# proto.net
KiCad netlist of a schematic drawn in EAGLE
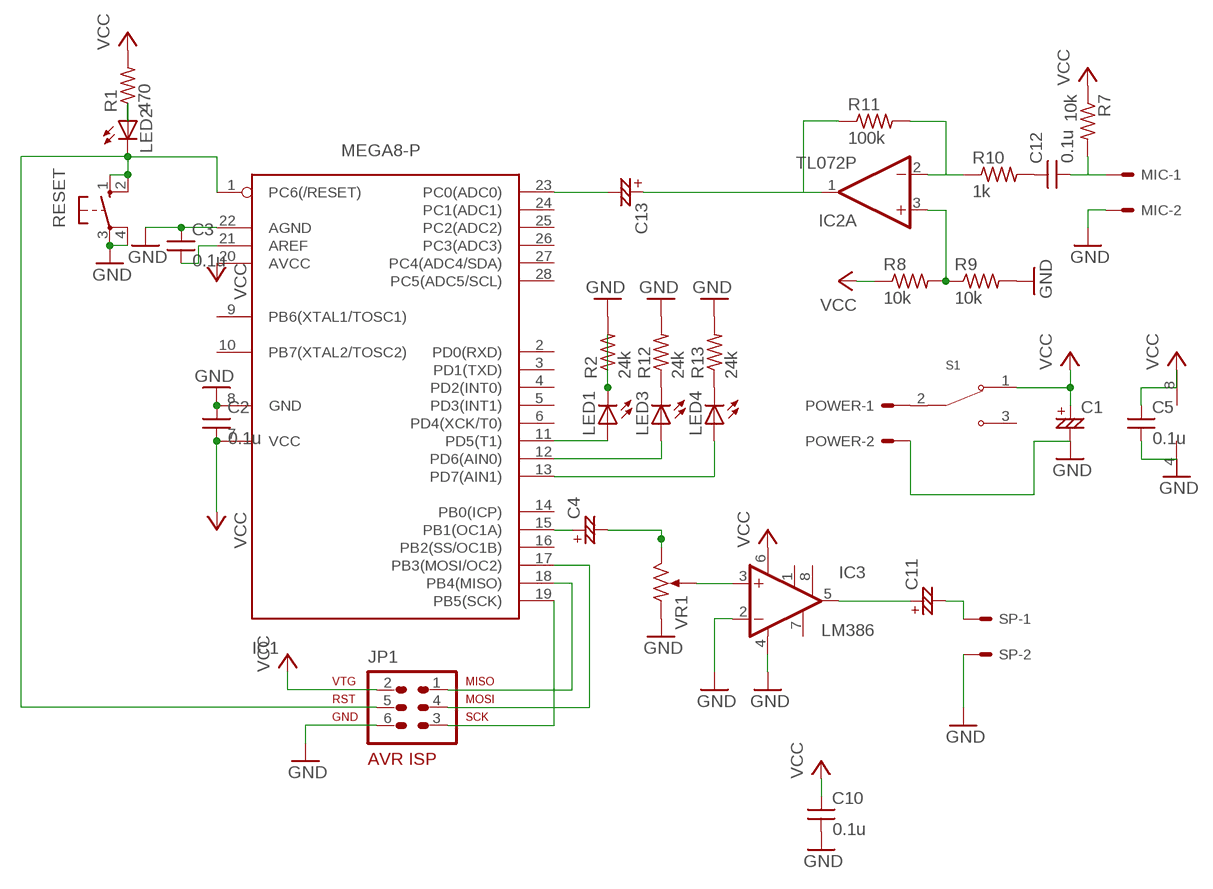
[diagram p0: schematic, sheet 1]

(export (version "E")
  (design (tool "Eeschema 10.0.6"))
  (components
    (comp (ref "C1")
      (value "E-CAPACITOR-2")
      (footprint "eagle-import:E3,5-8")
      (libsource (lib "eagle-import") (part "E-CAPACITOR-2"))
    )
    (comp (ref "C2")
      (value "0.1u")
      (footprint "eagle-import:C5B3")
      (libsource (lib "eagle-import") (part "C-CAPACITOR-2"))
    )
    (comp (ref "C3")
      (value "0.1u")
      (footprint "eagle-import:C5B3")
      (libsource (lib "eagle-import") (part "C-CAPACITOR-2"))
    )
    (comp (ref "C4")
      (value "E-CAPACITOR-2")
      (footprint "eagle-import:E3,5-8")
      (libsource (lib "eagle-import") (part "E-CAPACITOR-2"))
    )
    (comp (ref "C5")
      (value "0.1u")
      (footprint "eagle-import:C5B3")
      (libsource (lib "eagle-import") (part "C-CAPACITOR-2"))
    )
    (comp (ref "C10")
      (value "0.1u")
      (footprint "eagle-import:C5B3")
      (libsource (lib "eagle-import") (part "C-CAPACITOR-2"))
    )
    (comp (ref "C11")
      (value "E-CAPACITOR-2")
      (footprint "eagle-import:E3,5-8")
      (libsource (lib "eagle-import") (part "E-CAPACITOR-2"))
    )
    (comp (ref "C12")
      (value "0.1u")
      (footprint "eagle-import:C5B3")
      (libsource (lib "eagle-import") (part "C-CAPACITOR-2"))
    )
    (comp (ref "C13")
      (value "E-CAPACITOR-2")
      (footprint "eagle-import:E3,5-8")
      (libsource (lib "eagle-import") (part "E-CAPACITOR-2"))
    )
    (comp (ref "IC1")
      (value "MEGA8-P")
      (footprint "eagle-import:DIL28-3")
      (libsource (lib "eagle-import") (part "MEGA8-P"))
    )
    (comp (ref "IC2")
      (value "TL072P")
      (footprint "eagle-import:DIL08")
      (libsource (lib "eagle-import") (part "TL072P"))
    )
    (comp (ref "IC3")
      (value "LM386")
      (footprint "eagle-import:DIL08")
      (libsource (lib "eagle-import") (part "LM386"))
    )
    (comp (ref "JP1")
      (value "AVR-ISP-6")
      (footprint "eagle-import:AVR-ISP-6")
      (libsource (lib "eagle-import") (part "AVR-ISP-6"))
    )
    (comp (ref "LED1")
      (value "LED3MM")
      (footprint "eagle-import:LED3MM")
      (libsource (lib "eagle-import") (part "LED3MM"))
    )
    (comp (ref "LED2")
      (value "LED3MM")
      (footprint "eagle-import:LED3MM")
      (libsource (lib "eagle-import") (part "LED3MM"))
    )
    (comp (ref "LED3")
      (value "LED3MM")
      (footprint "eagle-import:LED3MM")
      (libsource (lib "eagle-import") (part "LED3MM"))
    )
    (comp (ref "LED4")
      (value "LED3MM")
      (footprint "eagle-import:LED3MM")
      (libsource (lib "eagle-import") (part "LED3MM"))
    )
    (comp (ref "MIC")
      (value "S2P-S")
      (footprint "eagle-import:2P-S")
      (libsource (lib "eagle-import") (part "S2P-S"))
    )
    (comp (ref "POWER")
      (value "S2P-S")
      (footprint "eagle-import:2P-S")
      (libsource (lib "eagle-import") (part "S2P-S"))
    )
    (comp (ref "R1")
      (value "470")
      (footprint "eagle-import:0207_3V")
      (libsource (lib "eagle-import") (part "RESISTOR-3V"))
    )
    (comp (ref "R2")
      (value "24k")
      (footprint "eagle-import:0207_3V")
      (libsource (lib "eagle-import") (part "RESISTOR-3V"))
    )
    (comp (ref "R7")
      (value "10k")
      (footprint "eagle-import:0207_3V")
      (libsource (lib "eagle-import") (part "RESISTOR-3V"))
    )
    (comp (ref "R8")
      (value "10k")
      (footprint "eagle-import:0207_3V")
      (libsource (lib "eagle-import") (part "RESISTOR-3V"))
    )
    (comp (ref "R9")
      (value "10k")
      (footprint "eagle-import:0207_3V")
      (libsource (lib "eagle-import") (part "RESISTOR-3V"))
    )
    (comp (ref "R10")
      (value "1k")
      (footprint "eagle-import:0207_3V")
      (libsource (lib "eagle-import") (part "RESISTOR-3V"))
    )
    (comp (ref "R11")
      (value "100k")
      (footprint "eagle-import:0207_3V")
      (libsource (lib "eagle-import") (part "RESISTOR-3V"))
    )
    (comp (ref "R12")
      (value "24k")
      (footprint "eagle-import:0207_3V")
      (libsource (lib "eagle-import") (part "RESISTOR-3V"))
    )
    (comp (ref "R13")
      (value "24k")
      (footprint "eagle-import:0207_3V")
      (libsource (lib "eagle-import") (part "RESISTOR-3V"))
    )
    (comp (ref "RESET")
      (value "10-XX")
      (footprint "eagle-import:B3F-10XX")
      (libsource (lib "eagle-import") (part "10-XX"))
    )
    (comp (ref "S1")
      (value "MS12ANW03")
      (footprint "eagle-import:SW_MS12ANW03")
      (fields (field (name "MF") "NKK Switches"))
      (libsource (lib "eagle-import") (part "MS12ANW03"))
    )
    (comp (ref "SP")
      (value "S2P-S")
      (footprint "eagle-import:2P-S")
      (libsource (lib "eagle-import") (part "S2P-S"))
    )
    (comp (ref "VR1")
      (value "V-RESISTOR")
      (footprint "eagle-import:B25X")
      (libsource (lib "eagle-import") (part "V-RESISTOR"))
    )
  )
  (nets
    (net (code "1") (name "/V-") (class "Default")
      (node (ref "IC2") (pin "4") (pinfunction "V-_4") (pintype "power_in"))
    )
    (net (code "2") (name "GND") (class "Default")
      (node (ref "C1") (pin "2") (pinfunction "2_2") (pintype "passive"))
      (node (ref "C10") (pin "2") (pinfunction "2_2") (pintype "passive"))
      (node (ref "C2") (pin "1") (pinfunction "1_1") (pintype "passive"))
      (node (ref "C3") (pin "1") (pinfunction "1_1") (pintype "passive"))
      (node (ref "C5") (pin "2") (pinfunction "2_2") (pintype "passive"))
      (node (ref "IC1") (pin "22") (pinfunction "AGND_22") (pintype "bidirectional"))
      (node (ref "IC1") (pin "8") (pinfunction "GND_8") (pintype "bidirectional"))
      (node (ref "IC3") (pin "2") (pinfunction "-IN_2") (pintype "input"))
      (node (ref "IC3") (pin "4") (pinfunction "V-_4") (pintype "power_in"))
      (node (ref "JP1") (pin "6") (pinfunction "6_6") (pintype "passive"))
      (node (ref "MIC") (pin "2") (pinfunction "S_2") (pintype "passive"))
      (node (ref "POWER") (pin "2") (pinfunction "S_2") (pintype "passive"))
      (node (ref "R12") (pin "2") (pinfunction "2_2") (pintype "passive"))
      (node (ref "R13") (pin "2") (pinfunction "2_2") (pintype "passive"))
      (node (ref "R2") (pin "2") (pinfunction "2_2") (pintype "passive"))
      (node (ref "R9") (pin "2") (pinfunction "2_2") (pintype "passive"))
      (node (ref "RESET") (pin "3") (pinfunction "P_3") (pintype "passive"))
      (node (ref "RESET") (pin "4") (pinfunction "P1_4") (pintype "passive"))
      (node (ref "SP") (pin "2") (pinfunction "S_2") (pintype "passive"))
      (node (ref "VR1") (pin "2") (pinfunction "2_2") (pintype "passive"))
    )
    (net (code "3") (name "Net-(C4-Pad2)") (class "Default")
      (node (ref "C4") (pin "2") (pinfunction "2_2") (pintype "passive"))
      (node (ref "VR1") (pin "1") (pinfunction "1_1") (pintype "passive"))
    )
    (net (code "4") (name "Net-(C12-Pad1)") (class "Default")
      (node (ref "C12") (pin "1") (pinfunction "1_1") (pintype "passive"))
      (node (ref "R10") (pin "2") (pinfunction "2_2") (pintype "passive"))
    )
    (net (code "5") (name "Net-(IC1-AREF)") (class "Default")
      (node (ref "C3") (pin "2") (pinfunction "2_2") (pintype "passive"))
      (node (ref "IC1") (pin "21") (pinfunction "AREF_21") (pintype "bidirectional"))
    )
    (net (code "6") (name "Net-(IC1-PB1(OC1A))") (class "Default")
      (node (ref "C4") (pin "1") (pinfunction "1_1") (pintype "passive"))
      (node (ref "IC1") (pin "15") (pinfunction "PB1(OC1A)_15") (pintype "bidirectional"))
    )
    (net (code "7") (name "Net-(IC1-PB3(MOSI{slash}OC2))") (class "Default")
      (node (ref "IC1") (pin "17") (pinfunction "PB3(MOSI/OC2)_17") (pintype "bidirectional"))
      (node (ref "JP1") (pin "4") (pinfunction "4_4") (pintype "passive"))
    )
    (net (code "8") (name "Net-(IC1-PB4(MISO))") (class "Default")
      (node (ref "IC1") (pin "18") (pinfunction "PB4(MISO)_18") (pintype "bidirectional"))
      (node (ref "JP1") (pin "1") (pinfunction "1_1") (pintype "passive"))
    )
    (net (code "9") (name "Net-(IC1-PB5(SCK))") (class "Default")
      (node (ref "IC1") (pin "19") (pinfunction "PB5(SCK)_19") (pintype "bidirectional"))
      (node (ref "JP1") (pin "3") (pinfunction "3_3") (pintype "passive"))
    )
    (net (code "10") (name "Net-(IC1-PC0(ADC0))") (class "Default")
      (node (ref "C13") (pin "2") (pinfunction "2_2") (pintype "passive"))
      (node (ref "IC1") (pin "23") (pinfunction "PC0(ADC0)_23") (pintype "bidirectional"))
    )
    (net (code "11") (name "Net-(IC1-PC6({slash}RESET))") (class "Default")
      (node (ref "IC1") (pin "1") (pinfunction "PC6(/RESET)_1") (pintype "bidirectional"))
      (node (ref "LED2") (pin "K") (pinfunction "C_K") (pintype "passive"))
      (node (ref "RESET") (pin "1") (pinfunction "S_1") (pintype "passive"))
      (node (ref "RESET") (pin "2") (pinfunction "S1_2") (pintype "passive"))
    )
    (net (code "12") (name "Net-(IC1-PD5(T1))") (class "Default")
      (node (ref "IC1") (pin "11") (pinfunction "PD5(T1)_11") (pintype "bidirectional"))
      (node (ref "LED1") (pin "A") (pinfunction "A_A") (pintype "passive"))
    )
    (net (code "13") (name "Net-(IC1-PD6(AIN0))") (class "Default")
      (node (ref "IC1") (pin "12") (pinfunction "PD6(AIN0)_12") (pintype "bidirectional"))
      (node (ref "LED3") (pin "A") (pinfunction "A_A") (pintype "passive"))
    )
    (net (code "14") (name "Net-(IC1-PD7(AIN1))") (class "Default")
      (node (ref "IC1") (pin "13") (pinfunction "PD7(AIN1)_13") (pintype "bidirectional"))
      (node (ref "LED4") (pin "A") (pinfunction "A_A") (pintype "passive"))
    )
    (net (code "15") (name "Net-(IC2A-+IN)") (class "Default")
      (node (ref "IC2") (pin "3") (pinfunction "+IN_3") (pintype "input"))
      (node (ref "R8") (pin "2") (pinfunction "2_2") (pintype "passive"))
      (node (ref "R9") (pin "1") (pinfunction "1_1") (pintype "passive"))
    )
    (net (code "16") (name "Net-(IC2A--IN)") (class "Default")
      (node (ref "IC2") (pin "2") (pinfunction "-IN_2") (pintype "input"))
      (node (ref "R10") (pin "1") (pinfunction "1_1") (pintype "passive"))
      (node (ref "R11") (pin "2") (pinfunction "2_2") (pintype "passive"))
    )
    (net (code "17") (name "Net-(IC2A-OUT)") (class "Default")
      (node (ref "C13") (pin "1") (pinfunction "1_1") (pintype "passive"))
      (node (ref "IC2") (pin "1") (pinfunction "OUT_1") (pintype "output"))
      (node (ref "R11") (pin "1") (pinfunction "1_1") (pintype "passive"))
    )
    (net (code "18") (name "Net-(IC3-+IN)") (class "Default")
      (node (ref "IC3") (pin "3") (pinfunction "+IN_3") (pintype "input"))
      (node (ref "VR1") (pin "3") (pinfunction "3_3") (pintype "passive"))
    )
    (net (code "19") (name "Net-(IC3-OUT)") (class "Default")
      (node (ref "C11") (pin "1") (pinfunction "1_1") (pintype "passive"))
      (node (ref "IC3") (pin "5") (pinfunction "OUT_5") (pintype "output"))
    )
    (net (code "20") (name "Net-(LED1-C)") (class "Default")
      (node (ref "LED1") (pin "K") (pinfunction "C_K") (pintype "passive"))
      (node (ref "R2") (pin "1") (pinfunction "1_1") (pintype "passive"))
    )
    (net (code "21") (name "Net-(LED2-PadA)") (class "Default")
      (node (ref "LED2") (pin "A") (pinfunction "A_A") (pintype "passive"))
      (node (ref "R1") (pin "1") (pinfunction "1_1") (pintype "passive"))
    )
    (net (code "22") (name "Net-(LED3-C)") (class "Default")
      (node (ref "LED3") (pin "K") (pinfunction "C_K") (pintype "passive"))
      (node (ref "R12") (pin "1") (pinfunction "1_1") (pintype "passive"))
    )
    (net (code "23") (name "Net-(LED4-C)") (class "Default")
      (node (ref "LED4") (pin "K") (pinfunction "C_K") (pintype "passive"))
      (node (ref "R13") (pin "1") (pinfunction "1_1") (pintype "passive"))
    )
    (net (code "24") (name "Net-(MICA-S)") (class "Default")
      (node (ref "C12") (pin "2") (pinfunction "2_2") (pintype "passive"))
      (node (ref "MIC") (pin "1") (pinfunction "S_1") (pintype "passive"))
      (node (ref "R7") (pin "2") (pinfunction "2_2") (pintype "passive"))
    )
    (net (code "25") (name "Net-(POWERA-S)") (class "Default")
      (node (ref "POWER") (pin "1") (pinfunction "S_1") (pintype "passive"))
      (node (ref "S1") (pin "2") (pinfunction "2_2") (pintype "passive"))
    )
    (net (code "26") (name "Net-(SPA-S)") (class "Default")
      (node (ref "C11") (pin "2") (pinfunction "2_2") (pintype "passive"))
      (node (ref "SP") (pin "1") (pinfunction "S_1") (pintype "passive"))
    )
    (net (code "27") (name "VCC") (class "Default")
      (node (ref "C1") (pin "1") (pinfunction "1_1") (pintype "passive"))
      (node (ref "C10") (pin "1") (pinfunction "1_1") (pintype "passive"))
      (node (ref "C2") (pin "2") (pinfunction "2_2") (pintype "passive"))
      (node (ref "C5") (pin "1") (pinfunction "1_1") (pintype "passive"))
      (node (ref "IC1") (pin "20") (pinfunction "AVCC_20") (pintype "bidirectional"))
      (node (ref "IC1") (pin "7") (pinfunction "VCC_7") (pintype "bidirectional"))
      (node (ref "IC2") (pin "8") (pinfunction "V+_8") (pintype "power_in"))
      (node (ref "IC3") (pin "6") (pinfunction "V+_6") (pintype "power_in"))
      (node (ref "JP1") (pin "2") (pinfunction "2_2") (pintype "passive"))
      (node (ref "R1") (pin "2") (pinfunction "2_2") (pintype "passive"))
      (node (ref "R7") (pin "1") (pinfunction "1_1") (pintype "passive"))
      (node (ref "R8") (pin "1") (pinfunction "1_1") (pintype "passive"))
      (node (ref "S1") (pin "1") (pinfunction "1_1") (pintype "passive"))
    )
    (net (code "28") (name "unconnected-(IC1-PB0(ICP)-Pad14)") (class "Default")
      (node (ref "IC1") (pin "14") (pinfunction "PB0(ICP)_14") (pintype "bidirectional"))
    )
    (net (code "29") (name "unconnected-(IC1-PB2(SS{slash}OC1B)-Pad16)") (class "Default")
      (node (ref "IC1") (pin "16") (pinfunction "PB2(SS/OC1B)_16") (pintype "bidirectional"))
    )
    (net (code "30") (name "unconnected-(IC1-PB6(XTAL1{slash}TOSC1)-Pad9)") (class "Default")
      (node (ref "IC1") (pin "9") (pinfunction "PB6(XTAL1/TOSC1)_9") (pintype "bidirectional"))
    )
    (net (code "31") (name "unconnected-(IC1-PB7(XTAL2{slash}TOSC2)-Pad10)") (class "Default")
      (node (ref "IC1") (pin "10") (pinfunction "PB7(XTAL2/TOSC2)_10") (pintype "bidirectional"))
    )
    (net (code "32") (name "unconnected-(IC1-PC1(ADC1)-Pad24)") (class "Default")
      (node (ref "IC1") (pin "24") (pinfunction "PC1(ADC1)_24") (pintype "bidirectional"))
    )
    (net (code "33") (name "unconnected-(IC1-PC2(ADC2)-Pad25)") (class "Default")
      (node (ref "IC1") (pin "25") (pinfunction "PC2(ADC2)_25") (pintype "bidirectional"))
    )
    (net (code "34") (name "unconnected-(IC1-PC3(ADC3)-Pad26)") (class "Default")
      (node (ref "IC1") (pin "26") (pinfunction "PC3(ADC3)_26") (pintype "bidirectional"))
    )
    (net (code "35") (name "unconnected-(IC1-PC4(ADC4{slash}SDA)-Pad27)") (class "Default")
      (node (ref "IC1") (pin "27") (pinfunction "PC4(ADC4/SDA)_27") (pintype "bidirectional"))
    )
    (net (code "36") (name "unconnected-(IC1-PC5(ADC5{slash}SCL)-Pad28)") (class "Default")
      (node (ref "IC1") (pin "28") (pinfunction "PC5(ADC5/SCL)_28") (pintype "bidirectional"))
    )
    (net (code "37") (name "unconnected-(IC1-PD0(RXD)-Pad2)") (class "Default")
      (node (ref "IC1") (pin "2") (pinfunction "PD0(RXD)_2") (pintype "bidirectional"))
    )
    (net (code "38") (name "unconnected-(IC1-PD1(TXD)-Pad3)") (class "Default")
      (node (ref "IC1") (pin "3") (pinfunction "PD1(TXD)_3") (pintype "bidirectional"))
    )
    (net (code "39") (name "unconnected-(IC1-PD2(INT0)-Pad4)") (class "Default")
      (node (ref "IC1") (pin "4") (pinfunction "PD2(INT0)_4") (pintype "bidirectional"))
    )
    (net (code "40") (name "unconnected-(IC1-PD3(INT1)-Pad5)") (class "Default")
      (node (ref "IC1") (pin "5") (pinfunction "PD3(INT1)_5") (pintype "bidirectional"))
    )
    (net (code "41") (name "unconnected-(IC1-PD4(XCK{slash}T0)-Pad6)") (class "Default")
      (node (ref "IC1") (pin "6") (pinfunction "PD4(XCK/T0)_6") (pintype "bidirectional"))
    )
    (net (code "42") (name "unconnected-(IC3-GAIN1-Pad1)") (class "Default")
      (node (ref "IC3") (pin "1") (pinfunction "GAIN1_1") (pintype "passive"))
    )
    (net (code "43") (name "unconnected-(IC3-GAIN2-Pad8)") (class "Default")
      (node (ref "IC3") (pin "8") (pinfunction "GAIN2_8") (pintype "passive"))
    )
    (net (code "44") (name "unconnected-(IC3-GND-Pad7)") (class "Default")
      (node (ref "IC3") (pin "7") (pinfunction "GND_7") (pintype "passive"))
    )
    (net (code "45") (name "unconnected-(JP1-Pad5)") (class "Default")
      (node (ref "JP1") (pin "5") (pinfunction "5_5") (pintype "passive"))
    )
    (net (code "46") (name "unconnected-(S1-Pad3)") (class "Default")
      (node (ref "S1") (pin "3") (pinfunction "3_3") (pintype "passive"))
    )
  )
)
